# LED_board.net
KiCad netlist of a schematic drawn in EAGLE
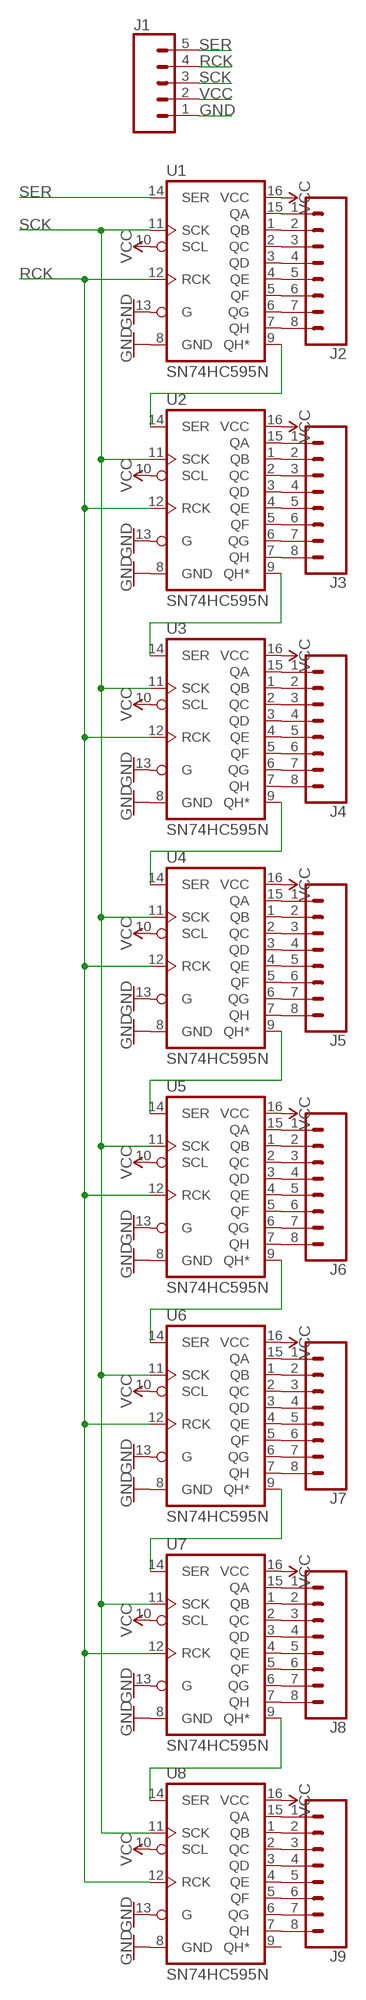
[diagram p0: schematic, sheet 1]

(export (version "E")
  (design (tool "Eeschema 10.0.6"))
  (components
    (comp (ref "J1")
      (value "CONN_05")
      (footprint "eagle-import:1X05")
      (libsource (lib "eagle-import") (part "CONN_05"))
    )
    (comp (ref "J2")
      (value "CONN_08\"")
      (footprint "eagle-import:1X08")
      (libsource (lib "eagle-import") (part "CONN_08{dblquote}"))
    )
    (comp (ref "J3")
      (value "CONN_08\"")
      (footprint "eagle-import:1X08")
      (libsource (lib "eagle-import") (part "CONN_08{dblquote}"))
    )
    (comp (ref "J4")
      (value "CONN_08\"")
      (footprint "eagle-import:1X08")
      (libsource (lib "eagle-import") (part "CONN_08{dblquote}"))
    )
    (comp (ref "J5")
      (value "CONN_08\"")
      (footprint "eagle-import:1X08")
      (libsource (lib "eagle-import") (part "CONN_08{dblquote}"))
    )
    (comp (ref "J6")
      (value "CONN_08\"")
      (footprint "eagle-import:1X08")
      (libsource (lib "eagle-import") (part "CONN_08{dblquote}"))
    )
    (comp (ref "J7")
      (value "CONN_08\"")
      (footprint "eagle-import:1X08")
      (libsource (lib "eagle-import") (part "CONN_08{dblquote}"))
    )
    (comp (ref "J8")
      (value "CONN_08\"")
      (footprint "eagle-import:1X08")
      (libsource (lib "eagle-import") (part "CONN_08{dblquote}"))
    )
    (comp (ref "J9")
      (value "CONN_08\"")
      (footprint "eagle-import:1X08")
      (libsource (lib "eagle-import") (part "CONN_08{dblquote}"))
    )
    (comp (ref "U1")
      (value "SN74HC595N")
      (footprint "eagle-import:DIP16")
      (libsource (lib "eagle-import") (part "74595NHC"))
    )
    (comp (ref "U2")
      (value "SN74HC595N")
      (footprint "eagle-import:DIP16")
      (libsource (lib "eagle-import") (part "74595NHC"))
    )
    (comp (ref "U3")
      (value "SN74HC595N")
      (footprint "eagle-import:DIP16")
      (libsource (lib "eagle-import") (part "74595NHC"))
    )
    (comp (ref "U4")
      (value "SN74HC595N")
      (footprint "eagle-import:DIP16")
      (libsource (lib "eagle-import") (part "74595NHC"))
    )
    (comp (ref "U5")
      (value "SN74HC595N")
      (footprint "eagle-import:DIP16")
      (libsource (lib "eagle-import") (part "74595NHC"))
    )
    (comp (ref "U6")
      (value "SN74HC595N")
      (footprint "eagle-import:DIP16")
      (libsource (lib "eagle-import") (part "74595NHC"))
    )
    (comp (ref "U7")
      (value "SN74HC595N")
      (footprint "eagle-import:DIP16")
      (libsource (lib "eagle-import") (part "74595NHC"))
    )
    (comp (ref "U8")
      (value "SN74HC595N")
      (footprint "eagle-import:DIP16")
      (libsource (lib "eagle-import") (part "74595NHC"))
    )
  )
  (nets
    (net (code "1") (name "/RCK") (class "Default")
      (node (ref "J1") (pin "4") (pinfunction "4_4") (pintype "passive"))
      (node (ref "U1") (pin "12") (pinfunction "RCK_12") (pintype "input"))
      (node (ref "U2") (pin "12") (pinfunction "RCK_12") (pintype "input"))
      (node (ref "U3") (pin "12") (pinfunction "RCK_12") (pintype "input"))
      (node (ref "U4") (pin "12") (pinfunction "RCK_12") (pintype "input"))
      (node (ref "U5") (pin "12") (pinfunction "RCK_12") (pintype "input"))
      (node (ref "U6") (pin "12") (pinfunction "RCK_12") (pintype "input"))
      (node (ref "U7") (pin "12") (pinfunction "RCK_12") (pintype "input"))
      (node (ref "U8") (pin "12") (pinfunction "RCK_12") (pintype "input"))
    )
    (net (code "2") (name "/SCK") (class "Default")
      (node (ref "J1") (pin "3") (pinfunction "3_3") (pintype "passive"))
      (node (ref "U1") (pin "11") (pinfunction "SCK_11") (pintype "input"))
      (node (ref "U2") (pin "11") (pinfunction "SCK_11") (pintype "input"))
      (node (ref "U3") (pin "11") (pinfunction "SCK_11") (pintype "input"))
      (node (ref "U4") (pin "11") (pinfunction "SCK_11") (pintype "input"))
      (node (ref "U5") (pin "11") (pinfunction "SCK_11") (pintype "input"))
      (node (ref "U6") (pin "11") (pinfunction "SCK_11") (pintype "input"))
      (node (ref "U7") (pin "11") (pinfunction "SCK_11") (pintype "input"))
      (node (ref "U8") (pin "11") (pinfunction "SCK_11") (pintype "input"))
    )
    (net (code "3") (name "/SER") (class "Default")
      (node (ref "J1") (pin "5") (pinfunction "5_5") (pintype "passive"))
      (node (ref "U1") (pin "14") (pinfunction "SER_14") (pintype "input"))
    )
    (net (code "4") (name "GND") (class "Default")
      (node (ref "J1") (pin "1") (pinfunction "1_1") (pintype "passive"))
      (node (ref "U1") (pin "13") (pinfunction "G_13") (pintype "input"))
      (node (ref "U1") (pin "8") (pinfunction "GND_8") (pintype "power_in"))
      (node (ref "U2") (pin "13") (pinfunction "G_13") (pintype "input"))
      (node (ref "U2") (pin "8") (pinfunction "GND_8") (pintype "power_in"))
      (node (ref "U3") (pin "13") (pinfunction "G_13") (pintype "input"))
      (node (ref "U3") (pin "8") (pinfunction "GND_8") (pintype "power_in"))
      (node (ref "U4") (pin "13") (pinfunction "G_13") (pintype "input"))
      (node (ref "U4") (pin "8") (pinfunction "GND_8") (pintype "power_in"))
      (node (ref "U5") (pin "13") (pinfunction "G_13") (pintype "input"))
      (node (ref "U5") (pin "8") (pinfunction "GND_8") (pintype "power_in"))
      (node (ref "U6") (pin "13") (pinfunction "G_13") (pintype "input"))
      (node (ref "U6") (pin "8") (pinfunction "GND_8") (pintype "power_in"))
      (node (ref "U7") (pin "13") (pinfunction "G_13") (pintype "input"))
      (node (ref "U7") (pin "8") (pinfunction "GND_8") (pintype "power_in"))
      (node (ref "U8") (pin "13") (pinfunction "G_13") (pintype "input"))
      (node (ref "U8") (pin "8") (pinfunction "GND_8") (pintype "power_in"))
    )
    (net (code "5") (name "Net-(U1-QA)") (class "Default")
      (node (ref "J2") (pin "1") (pinfunction "1_1") (pintype "passive"))
      (node (ref "U1") (pin "15") (pinfunction "QA_15") (pintype "tri_state"))
    )
    (net (code "6") (name "Net-(U1-QB)") (class "Default")
      (node (ref "J2") (pin "2") (pinfunction "2_2") (pintype "passive"))
      (node (ref "U1") (pin "1") (pinfunction "QB_1") (pintype "tri_state"))
    )
    (net (code "7") (name "Net-(U1-QC)") (class "Default")
      (node (ref "J2") (pin "3") (pinfunction "3_3") (pintype "passive"))
      (node (ref "U1") (pin "2") (pinfunction "QC_2") (pintype "tri_state"))
    )
    (net (code "8") (name "Net-(U1-QD)") (class "Default")
      (node (ref "J2") (pin "4") (pinfunction "4_4") (pintype "passive"))
      (node (ref "U1") (pin "3") (pinfunction "QD_3") (pintype "tri_state"))
    )
    (net (code "9") (name "Net-(U1-QE)") (class "Default")
      (node (ref "J2") (pin "5") (pinfunction "5_5") (pintype "passive"))
      (node (ref "U1") (pin "4") (pinfunction "QE_4") (pintype "tri_state"))
    )
    (net (code "10") (name "Net-(U1-QF)") (class "Default")
      (node (ref "J2") (pin "6") (pinfunction "6_6") (pintype "passive"))
      (node (ref "U1") (pin "5") (pinfunction "QF_5") (pintype "tri_state"))
    )
    (net (code "11") (name "Net-(U1-QG)") (class "Default")
      (node (ref "J2") (pin "7") (pinfunction "7_7") (pintype "passive"))
      (node (ref "U1") (pin "6") (pinfunction "QG_6") (pintype "tri_state"))
    )
    (net (code "12") (name "Net-(U1-QH)") (class "Default")
      (node (ref "J2") (pin "8") (pinfunction "8_8") (pintype "passive"))
      (node (ref "U1") (pin "7") (pinfunction "QH_7") (pintype "tri_state"))
    )
    (net (code "13") (name "Net-(U1-QH*)") (class "Default")
      (node (ref "U1") (pin "9") (pinfunction "QH*_9") (pintype "tri_state"))
      (node (ref "U2") (pin "14") (pinfunction "SER_14") (pintype "input"))
    )
    (net (code "14") (name "Net-(U2-QA)") (class "Default")
      (node (ref "J3") (pin "1") (pinfunction "1_1") (pintype "passive"))
      (node (ref "U2") (pin "15") (pinfunction "QA_15") (pintype "tri_state"))
    )
    (net (code "15") (name "Net-(U2-QB)") (class "Default")
      (node (ref "J3") (pin "2") (pinfunction "2_2") (pintype "passive"))
      (node (ref "U2") (pin "1") (pinfunction "QB_1") (pintype "tri_state"))
    )
    (net (code "16") (name "Net-(U2-QC)") (class "Default")
      (node (ref "J3") (pin "3") (pinfunction "3_3") (pintype "passive"))
      (node (ref "U2") (pin "2") (pinfunction "QC_2") (pintype "tri_state"))
    )
    (net (code "17") (name "Net-(U2-QD)") (class "Default")
      (node (ref "J3") (pin "4") (pinfunction "4_4") (pintype "passive"))
      (node (ref "U2") (pin "3") (pinfunction "QD_3") (pintype "tri_state"))
    )
    (net (code "18") (name "Net-(U2-QE)") (class "Default")
      (node (ref "J3") (pin "5") (pinfunction "5_5") (pintype "passive"))
      (node (ref "U2") (pin "4") (pinfunction "QE_4") (pintype "tri_state"))
    )
    (net (code "19") (name "Net-(U2-QF)") (class "Default")
      (node (ref "J3") (pin "6") (pinfunction "6_6") (pintype "passive"))
      (node (ref "U2") (pin "5") (pinfunction "QF_5") (pintype "tri_state"))
    )
    (net (code "20") (name "Net-(U2-QG)") (class "Default")
      (node (ref "J3") (pin "7") (pinfunction "7_7") (pintype "passive"))
      (node (ref "U2") (pin "6") (pinfunction "QG_6") (pintype "tri_state"))
    )
    (net (code "21") (name "Net-(U2-QH)") (class "Default")
      (node (ref "J3") (pin "8") (pinfunction "8_8") (pintype "passive"))
      (node (ref "U2") (pin "7") (pinfunction "QH_7") (pintype "tri_state"))
    )
    (net (code "22") (name "Net-(U2-QH*)") (class "Default")
      (node (ref "U2") (pin "9") (pinfunction "QH*_9") (pintype "tri_state"))
      (node (ref "U3") (pin "14") (pinfunction "SER_14") (pintype "input"))
    )
    (net (code "23") (name "Net-(U3-QA)") (class "Default")
      (node (ref "J4") (pin "1") (pinfunction "1_1") (pintype "passive"))
      (node (ref "U3") (pin "15") (pinfunction "QA_15") (pintype "tri_state"))
    )
    (net (code "24") (name "Net-(U3-QB)") (class "Default")
      (node (ref "J4") (pin "2") (pinfunction "2_2") (pintype "passive"))
      (node (ref "U3") (pin "1") (pinfunction "QB_1") (pintype "tri_state"))
    )
    (net (code "25") (name "Net-(U3-QC)") (class "Default")
      (node (ref "J4") (pin "3") (pinfunction "3_3") (pintype "passive"))
      (node (ref "U3") (pin "2") (pinfunction "QC_2") (pintype "tri_state"))
    )
    (net (code "26") (name "Net-(U3-QD)") (class "Default")
      (node (ref "J4") (pin "4") (pinfunction "4_4") (pintype "passive"))
      (node (ref "U3") (pin "3") (pinfunction "QD_3") (pintype "tri_state"))
    )
    (net (code "27") (name "Net-(U3-QE)") (class "Default")
      (node (ref "J4") (pin "5") (pinfunction "5_5") (pintype "passive"))
      (node (ref "U3") (pin "4") (pinfunction "QE_4") (pintype "tri_state"))
    )
    (net (code "28") (name "Net-(U3-QF)") (class "Default")
      (node (ref "J4") (pin "6") (pinfunction "6_6") (pintype "passive"))
      (node (ref "U3") (pin "5") (pinfunction "QF_5") (pintype "tri_state"))
    )
    (net (code "29") (name "Net-(U3-QG)") (class "Default")
      (node (ref "J4") (pin "7") (pinfunction "7_7") (pintype "passive"))
      (node (ref "U3") (pin "6") (pinfunction "QG_6") (pintype "tri_state"))
    )
    (net (code "30") (name "Net-(U3-QH)") (class "Default")
      (node (ref "J4") (pin "8") (pinfunction "8_8") (pintype "passive"))
      (node (ref "U3") (pin "7") (pinfunction "QH_7") (pintype "tri_state"))
    )
    (net (code "31") (name "Net-(U3-QH*)") (class "Default")
      (node (ref "U3") (pin "9") (pinfunction "QH*_9") (pintype "tri_state"))
      (node (ref "U4") (pin "14") (pinfunction "SER_14") (pintype "input"))
    )
    (net (code "32") (name "Net-(U4-QA)") (class "Default")
      (node (ref "J5") (pin "1") (pinfunction "1_1") (pintype "passive"))
      (node (ref "U4") (pin "15") (pinfunction "QA_15") (pintype "tri_state"))
    )
    (net (code "33") (name "Net-(U4-QB)") (class "Default")
      (node (ref "J5") (pin "2") (pinfunction "2_2") (pintype "passive"))
      (node (ref "U4") (pin "1") (pinfunction "QB_1") (pintype "tri_state"))
    )
    (net (code "34") (name "Net-(U4-QC)") (class "Default")
      (node (ref "J5") (pin "3") (pinfunction "3_3") (pintype "passive"))
      (node (ref "U4") (pin "2") (pinfunction "QC_2") (pintype "tri_state"))
    )
    (net (code "35") (name "Net-(U4-QD)") (class "Default")
      (node (ref "J5") (pin "4") (pinfunction "4_4") (pintype "passive"))
      (node (ref "U4") (pin "3") (pinfunction "QD_3") (pintype "tri_state"))
    )
    (net (code "36") (name "Net-(U4-QE)") (class "Default")
      (node (ref "J5") (pin "5") (pinfunction "5_5") (pintype "passive"))
      (node (ref "U4") (pin "4") (pinfunction "QE_4") (pintype "tri_state"))
    )
    (net (code "37") (name "Net-(U4-QF)") (class "Default")
      (node (ref "J5") (pin "6") (pinfunction "6_6") (pintype "passive"))
      (node (ref "U4") (pin "5") (pinfunction "QF_5") (pintype "tri_state"))
    )
    (net (code "38") (name "Net-(U4-QG)") (class "Default")
      (node (ref "J5") (pin "7") (pinfunction "7_7") (pintype "passive"))
      (node (ref "U4") (pin "6") (pinfunction "QG_6") (pintype "tri_state"))
    )
    (net (code "39") (name "Net-(U4-QH)") (class "Default")
      (node (ref "J5") (pin "8") (pinfunction "8_8") (pintype "passive"))
      (node (ref "U4") (pin "7") (pinfunction "QH_7") (pintype "tri_state"))
    )
    (net (code "40") (name "Net-(U4-QH*)") (class "Default")
      (node (ref "U4") (pin "9") (pinfunction "QH*_9") (pintype "tri_state"))
      (node (ref "U5") (pin "14") (pinfunction "SER_14") (pintype "input"))
    )
    (net (code "41") (name "Net-(U5-QA)") (class "Default")
      (node (ref "J6") (pin "1") (pinfunction "1_1") (pintype "passive"))
      (node (ref "U5") (pin "15") (pinfunction "QA_15") (pintype "tri_state"))
    )
    (net (code "42") (name "Net-(U5-QB)") (class "Default")
      (node (ref "J6") (pin "2") (pinfunction "2_2") (pintype "passive"))
      (node (ref "U5") (pin "1") (pinfunction "QB_1") (pintype "tri_state"))
    )
    (net (code "43") (name "Net-(U5-QC)") (class "Default")
      (node (ref "J6") (pin "3") (pinfunction "3_3") (pintype "passive"))
      (node (ref "U5") (pin "2") (pinfunction "QC_2") (pintype "tri_state"))
    )
    (net (code "44") (name "Net-(U5-QD)") (class "Default")
      (node (ref "J6") (pin "4") (pinfunction "4_4") (pintype "passive"))
      (node (ref "U5") (pin "3") (pinfunction "QD_3") (pintype "tri_state"))
    )
    (net (code "45") (name "Net-(U5-QE)") (class "Default")
      (node (ref "J6") (pin "5") (pinfunction "5_5") (pintype "passive"))
      (node (ref "U5") (pin "4") (pinfunction "QE_4") (pintype "tri_state"))
    )
    (net (code "46") (name "Net-(U5-QF)") (class "Default")
      (node (ref "J6") (pin "6") (pinfunction "6_6") (pintype "passive"))
      (node (ref "U5") (pin "5") (pinfunction "QF_5") (pintype "tri_state"))
    )
    (net (code "47") (name "Net-(U5-QG)") (class "Default")
      (node (ref "J6") (pin "7") (pinfunction "7_7") (pintype "passive"))
      (node (ref "U5") (pin "6") (pinfunction "QG_6") (pintype "tri_state"))
    )
    (net (code "48") (name "Net-(U5-QH)") (class "Default")
      (node (ref "J6") (pin "8") (pinfunction "8_8") (pintype "passive"))
      (node (ref "U5") (pin "7") (pinfunction "QH_7") (pintype "tri_state"))
    )
    (net (code "49") (name "Net-(U5-QH*)") (class "Default")
      (node (ref "U5") (pin "9") (pinfunction "QH*_9") (pintype "tri_state"))
      (node (ref "U6") (pin "14") (pinfunction "SER_14") (pintype "input"))
    )
    (net (code "50") (name "Net-(U6-QA)") (class "Default")
      (node (ref "J7") (pin "1") (pinfunction "1_1") (pintype "passive"))
      (node (ref "U6") (pin "15") (pinfunction "QA_15") (pintype "tri_state"))
    )
    (net (code "51") (name "Net-(U6-QB)") (class "Default")
      (node (ref "J7") (pin "2") (pinfunction "2_2") (pintype "passive"))
      (node (ref "U6") (pin "1") (pinfunction "QB_1") (pintype "tri_state"))
    )
    (net (code "52") (name "Net-(U6-QC)") (class "Default")
      (node (ref "J7") (pin "3") (pinfunction "3_3") (pintype "passive"))
      (node (ref "U6") (pin "2") (pinfunction "QC_2") (pintype "tri_state"))
    )
    (net (code "53") (name "Net-(U6-QD)") (class "Default")
      (node (ref "J7") (pin "4") (pinfunction "4_4") (pintype "passive"))
      (node (ref "U6") (pin "3") (pinfunction "QD_3") (pintype "tri_state"))
    )
    (net (code "54") (name "Net-(U6-QE)") (class "Default")
      (node (ref "J7") (pin "5") (pinfunction "5_5") (pintype "passive"))
      (node (ref "U6") (pin "4") (pinfunction "QE_4") (pintype "tri_state"))
    )
    (net (code "55") (name "Net-(U6-QF)") (class "Default")
      (node (ref "J7") (pin "6") (pinfunction "6_6") (pintype "passive"))
      (node (ref "U6") (pin "5") (pinfunction "QF_5") (pintype "tri_state"))
    )
    (net (code "56") (name "Net-(U6-QG)") (class "Default")
      (node (ref "J7") (pin "7") (pinfunction "7_7") (pintype "passive"))
      (node (ref "U6") (pin "6") (pinfunction "QG_6") (pintype "tri_state"))
    )
    (net (code "57") (name "Net-(U6-QH)") (class "Default")
      (node (ref "J7") (pin "8") (pinfunction "8_8") (pintype "passive"))
      (node (ref "U6") (pin "7") (pinfunction "QH_7") (pintype "tri_state"))
    )
    (net (code "58") (name "Net-(U6-QH*)") (class "Default")
      (node (ref "U6") (pin "9") (pinfunction "QH*_9") (pintype "tri_state"))
      (node (ref "U7") (pin "14") (pinfunction "SER_14") (pintype "input"))
    )
    (net (code "59") (name "Net-(U7-QA)") (class "Default")
      (node (ref "J8") (pin "1") (pinfunction "1_1") (pintype "passive"))
      (node (ref "U7") (pin "15") (pinfunction "QA_15") (pintype "tri_state"))
    )
    (net (code "60") (name "Net-(U7-QB)") (class "Default")
      (node (ref "J8") (pin "2") (pinfunction "2_2") (pintype "passive"))
      (node (ref "U7") (pin "1") (pinfunction "QB_1") (pintype "tri_state"))
    )
    (net (code "61") (name "Net-(U7-QC)") (class "Default")
      (node (ref "J8") (pin "3") (pinfunction "3_3") (pintype "passive"))
      (node (ref "U7") (pin "2") (pinfunction "QC_2") (pintype "tri_state"))
    )
    (net (code "62") (name "Net-(U7-QD)") (class "Default")
      (node (ref "J8") (pin "4") (pinfunction "4_4") (pintype "passive"))
      (node (ref "U7") (pin "3") (pinfunction "QD_3") (pintype "tri_state"))
    )
    (net (code "63") (name "Net-(U7-QE)") (class "Default")
      (node (ref "J8") (pin "5") (pinfunction "5_5") (pintype "passive"))
      (node (ref "U7") (pin "4") (pinfunction "QE_4") (pintype "tri_state"))
    )
    (net (code "64") (name "Net-(U7-QF)") (class "Default")
      (node (ref "J8") (pin "6") (pinfunction "6_6") (pintype "passive"))
      (node (ref "U7") (pin "5") (pinfunction "QF_5") (pintype "tri_state"))
    )
    (net (code "65") (name "Net-(U7-QG)") (class "Default")
      (node (ref "J8") (pin "7") (pinfunction "7_7") (pintype "passive"))
      (node (ref "U7") (pin "6") (pinfunction "QG_6") (pintype "tri_state"))
    )
    (net (code "66") (name "Net-(U7-QH)") (class "Default")
      (node (ref "J8") (pin "8") (pinfunction "8_8") (pintype "passive"))
      (node (ref "U7") (pin "7") (pinfunction "QH_7") (pintype "tri_state"))
    )
    (net (code "67") (name "Net-(U7-QH*)") (class "Default")
      (node (ref "U7") (pin "9") (pinfunction "QH*_9") (pintype "tri_state"))
      (node (ref "U8") (pin "14") (pinfunction "SER_14") (pintype "input"))
    )
    (net (code "68") (name "Net-(U8-QA)") (class "Default")
      (node (ref "J9") (pin "1") (pinfunction "1_1") (pintype "passive"))
      (node (ref "U8") (pin "15") (pinfunction "QA_15") (pintype "tri_state"))
    )
    (net (code "69") (name "Net-(U8-QB)") (class "Default")
      (node (ref "J9") (pin "2") (pinfunction "2_2") (pintype "passive"))
      (node (ref "U8") (pin "1") (pinfunction "QB_1") (pintype "tri_state"))
    )
    (net (code "70") (name "Net-(U8-QC)") (class "Default")
      (node (ref "J9") (pin "3") (pinfunction "3_3") (pintype "passive"))
      (node (ref "U8") (pin "2") (pinfunction "QC_2") (pintype "tri_state"))
    )
    (net (code "71") (name "Net-(U8-QD)") (class "Default")
      (node (ref "J9") (pin "4") (pinfunction "4_4") (pintype "passive"))
      (node (ref "U8") (pin "3") (pinfunction "QD_3") (pintype "tri_state"))
    )
    (net (code "72") (name "Net-(U8-QE)") (class "Default")
      (node (ref "J9") (pin "5") (pinfunction "5_5") (pintype "passive"))
      (node (ref "U8") (pin "4") (pinfunction "QE_4") (pintype "tri_state"))
    )
    (net (code "73") (name "Net-(U8-QF)") (class "Default")
      (node (ref "J9") (pin "6") (pinfunction "6_6") (pintype "passive"))
      (node (ref "U8") (pin "5") (pinfunction "QF_5") (pintype "tri_state"))
    )
    (net (code "74") (name "Net-(U8-QG)") (class "Default")
      (node (ref "J9") (pin "7") (pinfunction "7_7") (pintype "passive"))
      (node (ref "U8") (pin "6") (pinfunction "QG_6") (pintype "tri_state"))
    )
    (net (code "75") (name "Net-(U8-QH)") (class "Default")
      (node (ref "J9") (pin "8") (pinfunction "8_8") (pintype "passive"))
      (node (ref "U8") (pin "7") (pinfunction "QH_7") (pintype "tri_state"))
    )
    (net (code "76") (name "VCC") (class "Default")
      (node (ref "J1") (pin "2") (pinfunction "2_2") (pintype "passive"))
      (node (ref "U1") (pin "10") (pinfunction "SCL_10") (pintype "input"))
      (node (ref "U1") (pin "16") (pinfunction "VCC_16") (pintype "power_in"))
      (node (ref "U2") (pin "10") (pinfunction "SCL_10") (pintype "input"))
      (node (ref "U2") (pin "16") (pinfunction "VCC_16") (pintype "power_in"))
      (node (ref "U3") (pin "10") (pinfunction "SCL_10") (pintype "input"))
      (node (ref "U3") (pin "16") (pinfunction "VCC_16") (pintype "power_in"))
      (node (ref "U4") (pin "10") (pinfunction "SCL_10") (pintype "input"))
      (node (ref "U4") (pin "16") (pinfunction "VCC_16") (pintype "power_in"))
      (node (ref "U5") (pin "10") (pinfunction "SCL_10") (pintype "input"))
      (node (ref "U5") (pin "16") (pinfunction "VCC_16") (pintype "power_in"))
      (node (ref "U6") (pin "10") (pinfunction "SCL_10") (pintype "input"))
      (node (ref "U6") (pin "16") (pinfunction "VCC_16") (pintype "power_in"))
      (node (ref "U7") (pin "10") (pinfunction "SCL_10") (pintype "input"))
      (node (ref "U7") (pin "16") (pinfunction "VCC_16") (pintype "power_in"))
      (node (ref "U8") (pin "10") (pinfunction "SCL_10") (pintype "input"))
      (node (ref "U8") (pin "16") (pinfunction "VCC_16") (pintype "power_in"))
    )
    (net (code "77") (name "unconnected-(U8-QH*-Pad9)") (class "Default")
      (node (ref "U8") (pin "9") (pinfunction "QH*_9") (pintype "tri_state"))
    )
  )
)
